# Adafruit_Arcade_Bonnet.net
KiCad netlist of a schematic drawn in EAGLE
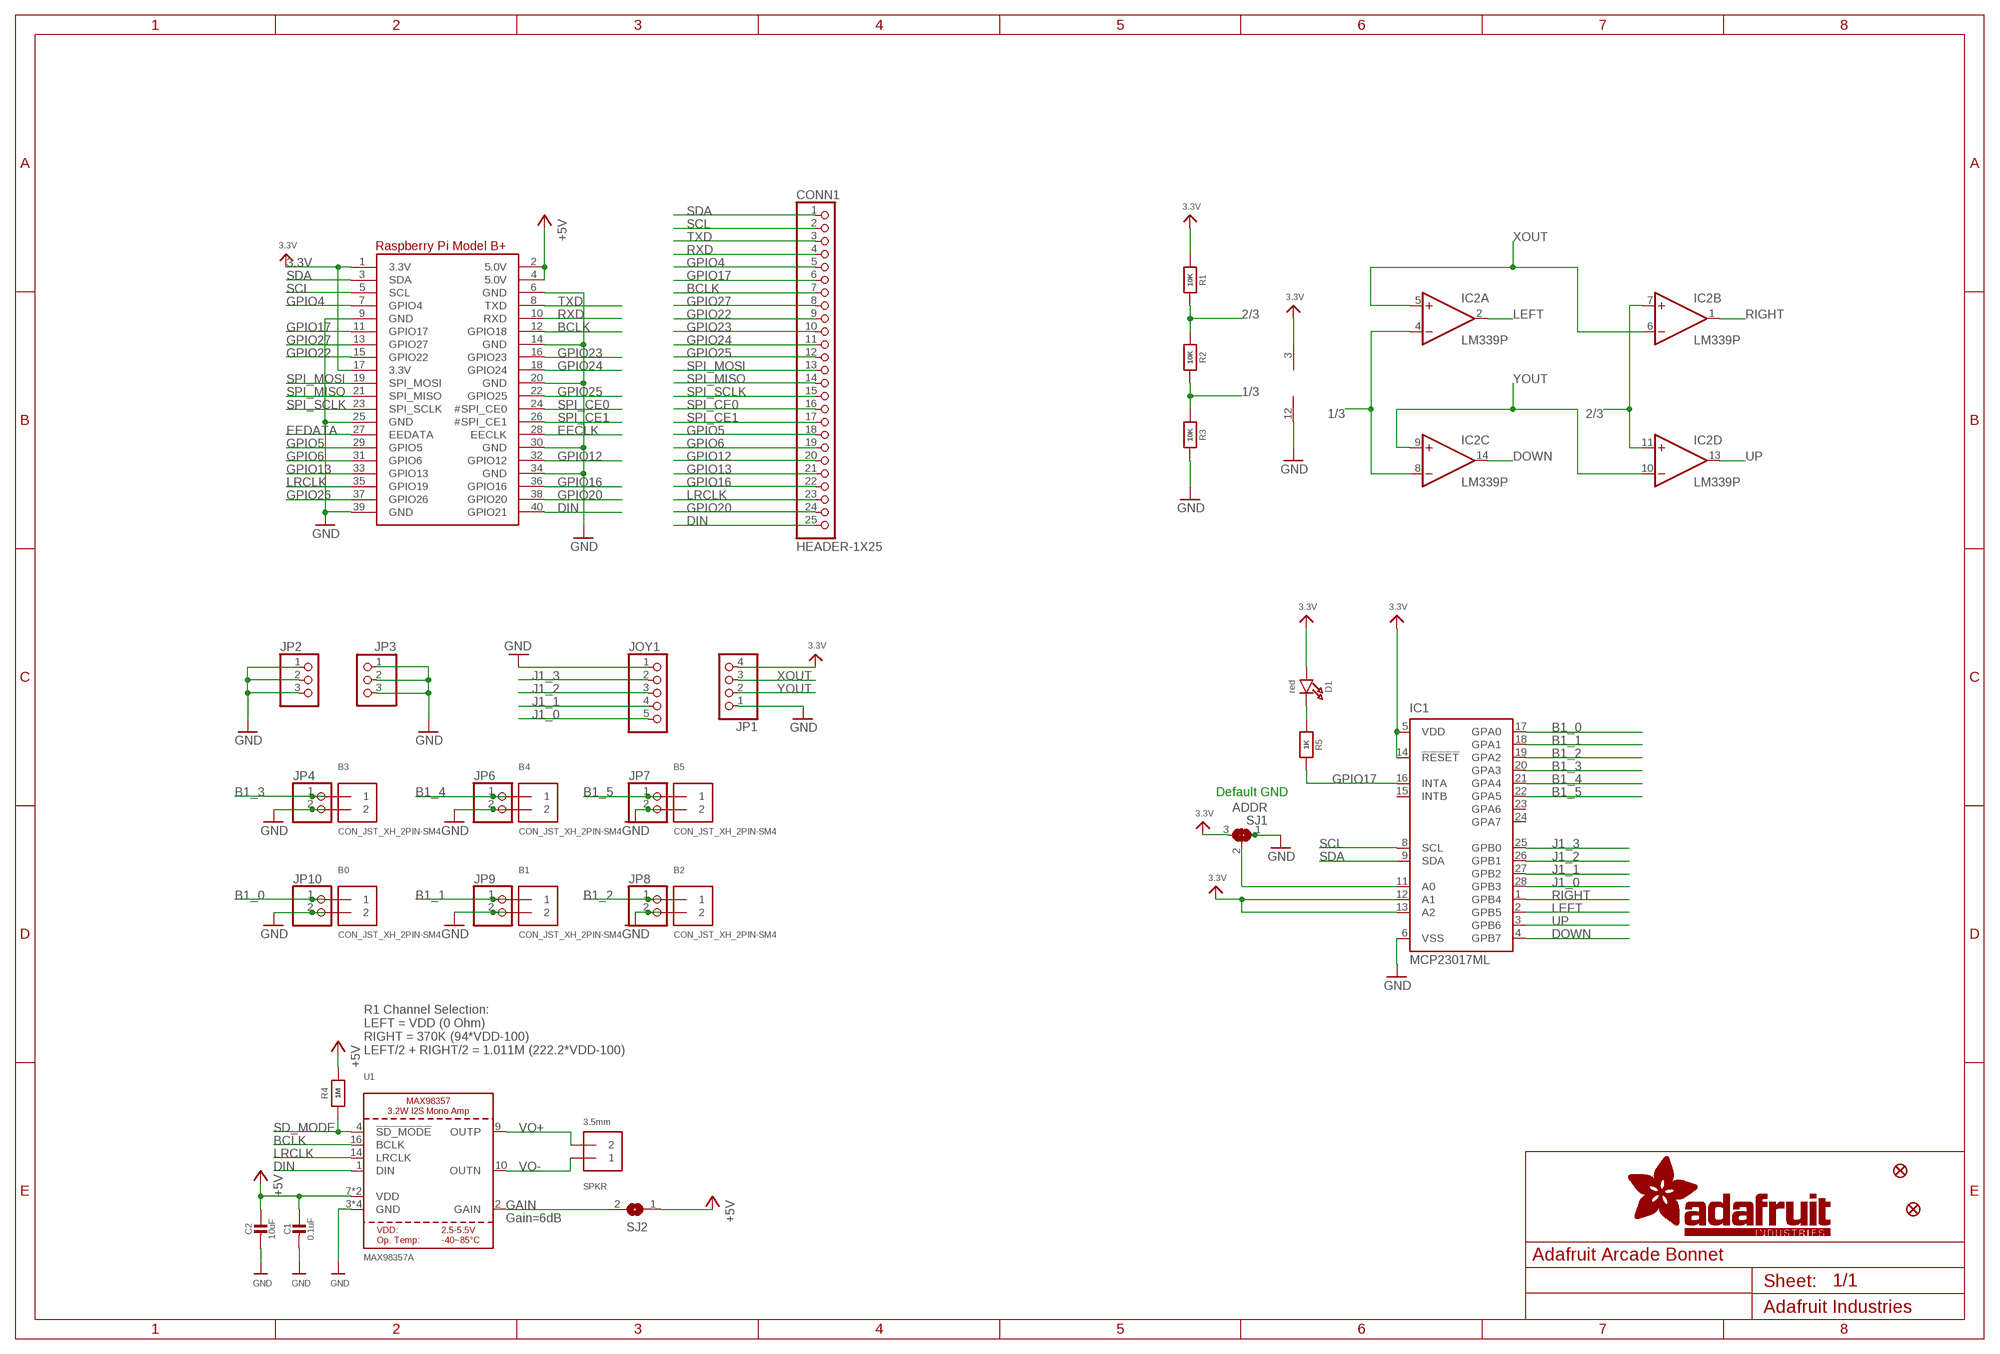
[diagram p0: schematic, sheet 1]

(export (version "E")
  (design (tool "Eeschema 10.0.6"))
  (components
    (comp (ref "B0")
      (value "CON_JST_XH_2PIN-SM4")
      (footprint "eagle-import:JST-XH-2-SM4")
      (libsource (lib "eagle-import") (part "CON_JST_XH_2PIN-SM4"))
    )
    (comp (ref "B1")
      (value "CON_JST_XH_2PIN-SM4")
      (footprint "eagle-import:JST-XH-2-SM4")
      (libsource (lib "eagle-import") (part "CON_JST_XH_2PIN-SM4"))
    )
    (comp (ref "B2")
      (value "CON_JST_XH_2PIN-SM4")
      (footprint "eagle-import:JST-XH-2-SM4")
      (libsource (lib "eagle-import") (part "CON_JST_XH_2PIN-SM4"))
    )
    (comp (ref "B3")
      (value "CON_JST_XH_2PIN-SM4")
      (footprint "eagle-import:JST-XH-2-SM4")
      (libsource (lib "eagle-import") (part "CON_JST_XH_2PIN-SM4"))
    )
    (comp (ref "B4")
      (value "CON_JST_XH_2PIN-SM4")
      (footprint "eagle-import:JST-XH-2-SM4")
      (libsource (lib "eagle-import") (part "CON_JST_XH_2PIN-SM4"))
    )
    (comp (ref "B5")
      (value "CON_JST_XH_2PIN-SM4")
      (footprint "eagle-import:JST-XH-2-SM4")
      (libsource (lib "eagle-import") (part "CON_JST_XH_2PIN-SM4"))
    )
    (comp (ref "C1")
      (value "0.1uF")
      (footprint "eagle-import:0603-NO")
      (libsource (lib "eagle-import") (part "CAP_CERAMIC0603_NO"))
    )
    (comp (ref "C2")
      (value "10uF")
      (footprint "eagle-import:0805-NO")
      (libsource (lib "eagle-import") (part "CAP_CERAMIC0805-NOOUTLINE"))
    )
    (comp (ref "CONN1")
      (value "HEADER-1X25")
      (footprint "eagle-import:1X25_ROUND_70MIL")
      (libsource (lib "eagle-import") (part "HEADER-1X25"))
    )
    (comp (ref "D1")
      (value "red")
      (footprint "eagle-import:CHIPLED_0805_NOOUTLINE")
      (libsource (lib "eagle-import") (part "LED0805_NOOUTLINE"))
    )
    (comp (ref "FID2")
      (value "FIDUCIAL\"\"")
      (footprint "eagle-import:FIDUCIAL_1MM")
      (libsource (lib "eagle-import") (part "FIDUCIAL{dblquote}{dblquote}"))
    )
    (comp (ref "FID3")
      (value "FIDUCIAL\"\"")
      (footprint "eagle-import:FIDUCIAL_1MM")
      (libsource (lib "eagle-import") (part "FIDUCIAL{dblquote}{dblquote}"))
    )
    (comp (ref "IC1")
      (value "MCP23017ML")
      (footprint "eagle-import:QFN28-ML_6X6MM")
      (fields
        (field (name "MF") "MICROCHIP")
        (field (name "MPN") "MCP23017-E/ML")
        (field (name "MPN_1") "MCP23017-E/SS")
        (field (name "OC_FARNELL") "1467674")
        (field (name "OC_NEWARK") "31K2960")
      )
      (libsource (lib "eagle-import") (part "MCP23017ML"))
    )
    (comp (ref "IC2")
      (value "LM339P")
      (footprint "eagle-import:TSSOP14")
      (libsource (lib "eagle-import") (part "LM339P"))
    )
    (comp (ref "JOY1")
      (value "HEADER-1X5")
      (footprint "eagle-import:1X05_OVAL")
      (libsource (lib "eagle-import") (part "HEADER-1X5"))
    )
    (comp (ref "JP1")
      (value "HEADER-1X4")
      (footprint "eagle-import:1X04_OVAL")
      (libsource (lib "eagle-import") (part "HEADER-1X4"))
    )
    (comp (ref "JP2")
      (value "HEADER-1X3ROUND")
      (footprint "eagle-import:1X03_ROUND")
      (libsource (lib "eagle-import") (part "HEADER-1X3ROUND"))
    )
    (comp (ref "JP3")
      (value "HEADER-1X3ROUND")
      (footprint "eagle-import:1X03_ROUND")
      (libsource (lib "eagle-import") (part "HEADER-1X3ROUND"))
    )
    (comp (ref "JP4")
      (value "HEADER-1X2")
      (footprint "eagle-import:1X02_OVAL")
      (libsource (lib "eagle-import") (part "HEADER-1X2"))
    )
    (comp (ref "JP6")
      (value "HEADER-1X2")
      (footprint "eagle-import:1X02_OVAL")
      (libsource (lib "eagle-import") (part "HEADER-1X2"))
    )
    (comp (ref "JP7")
      (value "HEADER-1X2")
      (footprint "eagle-import:1X02_OVAL")
      (libsource (lib "eagle-import") (part "HEADER-1X2"))
    )
    (comp (ref "JP8")
      (value "HEADER-1X2")
      (footprint "eagle-import:1X02_OVAL")
      (libsource (lib "eagle-import") (part "HEADER-1X2"))
    )
    (comp (ref "JP9")
      (value "HEADER-1X2")
      (footprint "eagle-import:1X02_OVAL")
      (libsource (lib "eagle-import") (part "HEADER-1X2"))
    )
    (comp (ref "JP10")
      (value "HEADER-1X2")
      (footprint "eagle-import:1X02_OVAL")
      (libsource (lib "eagle-import") (part "HEADER-1X2"))
    )
    (comp (ref "R1")
      (value "10K")
      (footprint "eagle-import:0805_10MGAP")
      (libsource (lib "eagle-import") (part "RESISTOR0805_10MGAP"))
    )
    (comp (ref "R2")
      (value "10K")
      (footprint "eagle-import:0805-NO")
      (libsource (lib "eagle-import") (part "RESISTOR0805_NOOUTLINE"))
    )
    (comp (ref "R3")
      (value "10K")
      (footprint "eagle-import:0805-NO")
      (libsource (lib "eagle-import") (part "RESISTOR0805_NOOUTLINE"))
    )
    (comp (ref "R4")
      (value "1M")
      (footprint "eagle-import:0603-NO")
      (libsource (lib "eagle-import") (part "RESISTOR_0603_NOOUT"))
    )
    (comp (ref "R5")
      (value "1K")
      (footprint "eagle-import:0603-NO")
      (libsource (lib "eagle-import") (part "RESISTOR_0603_NOOUT"))
    )
    (comp (ref "RPI1")
      (value "RASPBERRYPI_BPLUS_PHAT")
      (footprint "eagle-import:PI_BONNET")
      (libsource (lib "eagle-import") (part "RASPBERRYPI_BPLUS_PHAT"))
    )
    (comp (ref "SJ1")
      (value "ADDR")
      (footprint "eagle-import:SOLDERJUMPER_2WAY_OPEN_NOPASTE")
      (libsource (lib "eagle-import") (part "SOLDERJUMPER_2WAY"))
    )
    (comp (ref "SJ2")
      (value "SOLDERJUMPERCLOSED")
      (footprint "eagle-import:SOLDERJUMPER_CLOSEDWIRE")
      (libsource (lib "eagle-import") (part "SOLDERJUMPERCLOSED"))
    )
    (comp (ref "SPKR")
      (value "3.5mm")
      (footprint "eagle-import:TERMBLOCK_1X2-3.5MM")
      (libsource (lib "eagle-import") (part "TERMBLOCK_1X2"))
    )
    (comp (ref "U1")
      (value "MAX98357A")
      (footprint "eagle-import:QFN16_3MM")
      (libsource (lib "eagle-import") (part "AUDIOAMP_MAX98357"))
    )
  )
  (nets
    (net (code "1") (name "+5V") (class "Default")
      (node (ref "C1") (pin "1") (pinfunction "1_1") (pintype "passive"))
      (node (ref "C2") (pin "1") (pinfunction "1_1") (pintype "passive"))
      (node (ref "R4") (pin "2") (pinfunction "2_2") (pintype "passive"))
      (node (ref "RPI1") (pin "2") (pinfunction "5.0V_2") (pintype "power_in"))
      (node (ref "RPI1") (pin "4") (pinfunction "5.0V_4") (pintype "power_in"))
      (node (ref "SJ2") (pin "1") (pinfunction "1_1") (pintype "passive"))
      (node (ref "U1") (pin "7") (pinfunction "VDD_7") (pintype "power_in"))
      (node (ref "U1") (pin "8") (pinfunction "VDD_8") (pintype "power_in"))
    )
    (net (code "2") (name "/1{slash}3") (class "Default")
      (node (ref "IC2") (pin "4") (pinfunction "-IN_4") (pintype "input"))
      (node (ref "IC2") (pin "8") (pinfunction "-IN_8") (pintype "input"))
      (node (ref "R2") (pin "2") (pinfunction "2_2") (pintype "passive"))
      (node (ref "R3") (pin "1") (pinfunction "1_1") (pintype "passive"))
    )
    (net (code "3") (name "/2{slash}3") (class "Default")
      (node (ref "IC2") (pin "11") (pinfunction "+IN_11") (pintype "input"))
      (node (ref "IC2") (pin "7") (pinfunction "+IN_7") (pintype "input"))
      (node (ref "R1") (pin "2") (pinfunction "2_2") (pintype "passive"))
      (node (ref "R2") (pin "1") (pinfunction "1_1") (pintype "passive"))
    )
    (net (code "4") (name "/B1_0") (class "Default")
      (node (ref "B0") (pin "1") (pinfunction "1_1") (pintype "passive"))
      (node (ref "IC1") (pin "17") (pinfunction "GPA0_17") (pintype "bidirectional"))
      (node (ref "JP10") (pin "1") (pinfunction "1_1") (pintype "passive"))
    )
    (net (code "5") (name "/B1_1") (class "Default")
      (node (ref "B1") (pin "1") (pinfunction "1_1") (pintype "passive"))
      (node (ref "IC1") (pin "18") (pinfunction "GPA1_18") (pintype "bidirectional"))
      (node (ref "JP9") (pin "1") (pinfunction "1_1") (pintype "passive"))
    )
    (net (code "6") (name "/B1_2") (class "Default")
      (node (ref "B2") (pin "1") (pinfunction "1_1") (pintype "passive"))
      (node (ref "IC1") (pin "19") (pinfunction "GPA2_19") (pintype "bidirectional"))
      (node (ref "JP8") (pin "1") (pinfunction "1_1") (pintype "passive"))
    )
    (net (code "7") (name "/B1_3") (class "Default")
      (node (ref "B3") (pin "1") (pinfunction "1_1") (pintype "passive"))
      (node (ref "IC1") (pin "20") (pinfunction "GPA3_20") (pintype "bidirectional"))
      (node (ref "JP4") (pin "1") (pinfunction "1_1") (pintype "passive"))
    )
    (net (code "8") (name "/B1_4") (class "Default")
      (node (ref "B4") (pin "1") (pinfunction "1_1") (pintype "passive"))
      (node (ref "IC1") (pin "21") (pinfunction "GPA4_21") (pintype "bidirectional"))
      (node (ref "JP6") (pin "1") (pinfunction "1_1") (pintype "passive"))
    )
    (net (code "9") (name "/B1_5") (class "Default")
      (node (ref "B5") (pin "1") (pinfunction "1_1") (pintype "passive"))
      (node (ref "IC1") (pin "22") (pinfunction "GPA5_22") (pintype "bidirectional"))
      (node (ref "JP7") (pin "1") (pinfunction "1_1") (pintype "passive"))
    )
    (net (code "10") (name "/BCLK") (class "Default")
      (node (ref "CONN1") (pin "7") (pinfunction "7_7") (pintype "passive"))
      (node (ref "RPI1") (pin "12") (pinfunction "GPIO18_12") (pintype "bidirectional"))
      (node (ref "U1") (pin "16") (pinfunction "BCLK_16") (pintype "bidirectional"))
    )
    (net (code "11") (name "/DIN") (class "Default")
      (node (ref "CONN1") (pin "25") (pinfunction "25_25") (pintype "passive"))
      (node (ref "RPI1") (pin "40") (pinfunction "GPIO21_40") (pintype "bidirectional"))
      (node (ref "U1") (pin "1") (pinfunction "DIN_1") (pintype "bidirectional"))
    )
    (net (code "12") (name "/DOWN") (class "Default")
      (node (ref "IC1") (pin "4") (pinfunction "GPB7_4") (pintype "bidirectional"))
      (node (ref "IC2") (pin "14") (pinfunction "OUT_14") (pintype "open_collector"))
    )
    (net (code "13") (name "/EECLK") (class "Default")
      (node (ref "RPI1") (pin "28") (pinfunction "EECLK_28") (pintype "bidirectional"))
    )
    (net (code "14") (name "/EEDATA") (class "Default")
      (node (ref "RPI1") (pin "27") (pinfunction "EEDATA_27") (pintype "bidirectional"))
    )
    (net (code "15") (name "/GAIN") (class "Default")
      (node (ref "SJ2") (pin "2") (pinfunction "2_2") (pintype "passive"))
      (node (ref "U1") (pin "2") (pinfunction "GAIN_2") (pintype "bidirectional"))
    )
    (net (code "16") (name "/GPIO4") (class "Default")
      (node (ref "CONN1") (pin "5") (pinfunction "5_5") (pintype "passive"))
      (node (ref "RPI1") (pin "7") (pinfunction "GPIO4_7") (pintype "bidirectional"))
    )
    (net (code "17") (name "/GPIO5") (class "Default")
      (node (ref "CONN1") (pin "18") (pinfunction "18_18") (pintype "passive"))
      (node (ref "RPI1") (pin "29") (pinfunction "GPIO5_29") (pintype "bidirectional"))
    )
    (net (code "18") (name "/GPIO6") (class "Default")
      (node (ref "CONN1") (pin "19") (pinfunction "19_19") (pintype "passive"))
      (node (ref "RPI1") (pin "31") (pinfunction "GPIO6_31") (pintype "bidirectional"))
    )
    (net (code "19") (name "/GPIO12") (class "Default")
      (node (ref "CONN1") (pin "20") (pinfunction "20_20") (pintype "passive"))
      (node (ref "RPI1") (pin "32") (pinfunction "GPIO12_32") (pintype "bidirectional"))
    )
    (net (code "20") (name "/GPIO13") (class "Default")
      (node (ref "CONN1") (pin "21") (pinfunction "21_21") (pintype "passive"))
      (node (ref "RPI1") (pin "33") (pinfunction "GPIO13_33") (pintype "bidirectional"))
    )
    (net (code "21") (name "/GPIO16") (class "Default")
      (node (ref "CONN1") (pin "22") (pinfunction "22_22") (pintype "passive"))
      (node (ref "RPI1") (pin "36") (pinfunction "GPIO16_36") (pintype "bidirectional"))
    )
    (net (code "22") (name "/GPIO17") (class "Default")
      (node (ref "CONN1") (pin "6") (pinfunction "6_6") (pintype "passive"))
      (node (ref "IC1") (pin "16") (pinfunction "INTA_16") (pintype "output"))
      (node (ref "R5") (pin "2") (pinfunction "2_2") (pintype "passive"))
      (node (ref "RPI1") (pin "11") (pinfunction "GPIO17_11") (pintype "bidirectional"))
    )
    (net (code "23") (name "/GPIO20") (class "Default")
      (node (ref "CONN1") (pin "24") (pinfunction "24_24") (pintype "passive"))
      (node (ref "RPI1") (pin "38") (pinfunction "GPIO20_38") (pintype "bidirectional"))
    )
    (net (code "24") (name "/GPIO22") (class "Default")
      (node (ref "CONN1") (pin "9") (pinfunction "9_9") (pintype "passive"))
      (node (ref "RPI1") (pin "15") (pinfunction "GPIO22_15") (pintype "bidirectional"))
    )
    (net (code "25") (name "/GPIO23") (class "Default")
      (node (ref "CONN1") (pin "10") (pinfunction "10_10") (pintype "passive"))
      (node (ref "RPI1") (pin "16") (pinfunction "GPIO23_16") (pintype "bidirectional"))
    )
    (net (code "26") (name "/GPIO24") (class "Default")
      (node (ref "CONN1") (pin "11") (pinfunction "11_11") (pintype "passive"))
      (node (ref "RPI1") (pin "18") (pinfunction "GPIO24_18") (pintype "bidirectional"))
    )
    (net (code "27") (name "/GPIO25") (class "Default")
      (node (ref "CONN1") (pin "12") (pinfunction "12_12") (pintype "passive"))
      (node (ref "RPI1") (pin "22") (pinfunction "GPIO25_22") (pintype "bidirectional"))
    )
    (net (code "28") (name "/GPIO26") (class "Default")
      (node (ref "RPI1") (pin "37") (pinfunction "GPIO26_37") (pintype "bidirectional"))
    )
    (net (code "29") (name "/GPIO27") (class "Default")
      (node (ref "CONN1") (pin "8") (pinfunction "8_8") (pintype "passive"))
      (node (ref "RPI1") (pin "13") (pinfunction "GPIO27_13") (pintype "bidirectional"))
    )
    (net (code "30") (name "/J1_0") (class "Default")
      (node (ref "IC1") (pin "28") (pinfunction "GPB3_28") (pintype "bidirectional"))
      (node (ref "JOY1") (pin "5") (pinfunction "5_5") (pintype "passive"))
    )
    (net (code "31") (name "/J1_1") (class "Default")
      (node (ref "IC1") (pin "27") (pinfunction "GPB2_27") (pintype "bidirectional"))
      (node (ref "JOY1") (pin "4") (pinfunction "4_4") (pintype "passive"))
    )
    (net (code "32") (name "/J1_2") (class "Default")
      (node (ref "IC1") (pin "26") (pinfunction "GPB1_26") (pintype "bidirectional"))
      (node (ref "JOY1") (pin "3") (pinfunction "3_3") (pintype "passive"))
    )
    (net (code "33") (name "/J1_3") (class "Default")
      (node (ref "IC1") (pin "25") (pinfunction "GPB0_25") (pintype "bidirectional"))
      (node (ref "JOY1") (pin "2") (pinfunction "2_2") (pintype "passive"))
    )
    (net (code "34") (name "/LEFT") (class "Default")
      (node (ref "IC1") (pin "2") (pinfunction "GPB5_2") (pintype "bidirectional"))
      (node (ref "IC2") (pin "2") (pinfunction "OUT_2") (pintype "open_collector"))
    )
    (net (code "35") (name "/LRCLK") (class "Default")
      (node (ref "CONN1") (pin "23") (pinfunction "23_23") (pintype "passive"))
      (node (ref "RPI1") (pin "35") (pinfunction "GPIO19_35") (pintype "bidirectional"))
      (node (ref "U1") (pin "14") (pinfunction "LRCLK_14") (pintype "bidirectional"))
    )
    (net (code "36") (name "/RIGHT") (class "Default")
      (node (ref "IC1") (pin "1") (pinfunction "GPB4_1") (pintype "bidirectional"))
      (node (ref "IC2") (pin "1") (pinfunction "OUT_1") (pintype "open_collector"))
    )
    (net (code "37") (name "/RXD") (class "Default")
      (node (ref "CONN1") (pin "4") (pinfunction "4_4") (pintype "passive"))
      (node (ref "RPI1") (pin "10") (pinfunction "RXD_10") (pintype "bidirectional"))
    )
    (net (code "38") (name "/SCL") (class "Default")
      (node (ref "CONN1") (pin "2") (pinfunction "2_2") (pintype "passive"))
      (node (ref "IC1") (pin "8") (pinfunction "SCL_8") (pintype "input"))
      (node (ref "RPI1") (pin "5") (pinfunction "SCL_5") (pintype "bidirectional"))
    )
    (net (code "39") (name "/SDA") (class "Default")
      (node (ref "CONN1") (pin "1") (pinfunction "1_1") (pintype "passive"))
      (node (ref "IC1") (pin "9") (pinfunction "SDA_9") (pintype "bidirectional"))
      (node (ref "RPI1") (pin "3") (pinfunction "SDA_3") (pintype "bidirectional"))
    )
    (net (code "40") (name "/SD_MODE") (class "Default")
      (node (ref "R4") (pin "1") (pinfunction "1_1") (pintype "passive"))
      (node (ref "U1") (pin "4") (pinfunction "~{SD_MODE}_4") (pintype "bidirectional"))
    )
    (net (code "41") (name "/SPI_CE0") (class "Default")
      (node (ref "CONN1") (pin "16") (pinfunction "16_16") (pintype "passive"))
      (node (ref "RPI1") (pin "24") (pinfunction "#SPI_CE0_24") (pintype "bidirectional"))
    )
    (net (code "42") (name "/SPI_CE1") (class "Default")
      (node (ref "CONN1") (pin "17") (pinfunction "17_17") (pintype "passive"))
      (node (ref "RPI1") (pin "26") (pinfunction "#SPI_CE1_26") (pintype "bidirectional"))
    )
    (net (code "43") (name "/SPI_MISO") (class "Default")
      (node (ref "CONN1") (pin "14") (pinfunction "14_14") (pintype "passive"))
      (node (ref "RPI1") (pin "21") (pinfunction "SPI_MISO_21") (pintype "bidirectional"))
    )
    (net (code "44") (name "/SPI_MOSI") (class "Default")
      (node (ref "CONN1") (pin "13") (pinfunction "13_13") (pintype "passive"))
      (node (ref "RPI1") (pin "19") (pinfunction "SPI_MOSI_19") (pintype "bidirectional"))
    )
    (net (code "45") (name "/SPI_SCLK") (class "Default")
      (node (ref "CONN1") (pin "15") (pinfunction "15_15") (pintype "passive"))
      (node (ref "RPI1") (pin "23") (pinfunction "SPI_SCLK_23") (pintype "bidirectional"))
    )
    (net (code "46") (name "/TXD") (class "Default")
      (node (ref "CONN1") (pin "3") (pinfunction "3_3") (pintype "passive"))
      (node (ref "RPI1") (pin "8") (pinfunction "TXD_8") (pintype "bidirectional"))
    )
    (net (code "47") (name "/UP") (class "Default")
      (node (ref "IC1") (pin "3") (pinfunction "GPB6_3") (pintype "bidirectional"))
      (node (ref "IC2") (pin "13") (pinfunction "OUT_13") (pintype "open_collector"))
    )
    (net (code "48") (name "/VO+") (class "Default")
      (node (ref "SPKR") (pin "2") (pinfunction "2_2") (pintype "passive"))
      (node (ref "U1") (pin "9") (pinfunction "OUTP_9") (pintype "output"))
    )
    (net (code "49") (name "/VO-") (class "Default")
      (node (ref "SPKR") (pin "1") (pinfunction "1_1") (pintype "passive"))
      (node (ref "U1") (pin "10") (pinfunction "OUTN_10") (pintype "output"))
    )
    (net (code "50") (name "/XOUT") (class "Default")
      (node (ref "IC2") (pin "5") (pinfunction "+IN_5") (pintype "input"))
      (node (ref "IC2") (pin "6") (pinfunction "-IN_6") (pintype "input"))
      (node (ref "JP1") (pin "3") (pinfunction "3_3") (pintype "passive"))
    )
    (net (code "51") (name "/YOUT") (class "Default")
      (node (ref "IC2") (pin "10") (pinfunction "-IN_10") (pintype "input"))
      (node (ref "IC2") (pin "9") (pinfunction "+IN_9") (pintype "input"))
      (node (ref "JP1") (pin "2") (pinfunction "2_2") (pintype "passive"))
    )
    (net (code "52") (name "3.3V") (class "Default")
      (node (ref "D1") (pin "A") (pinfunction "A_A") (pintype "passive"))
      (node (ref "IC1") (pin "12") (pinfunction "A1_12") (pintype "input"))
      (node (ref "IC1") (pin "13") (pinfunction "A2_13") (pintype "input"))
      (node (ref "IC1") (pin "14") (pinfunction "~{RESET}_14") (pintype "input"))
      (node (ref "IC1") (pin "5") (pinfunction "VDD_5") (pintype "power_in"))
      (node (ref "IC2") (pin "3") (pinfunction "V+_3") (pintype "power_in"))
      (node (ref "JP1") (pin "4") (pinfunction "4_4") (pintype "passive"))
      (node (ref "R1") (pin "1") (pinfunction "1_1") (pintype "passive"))
      (node (ref "RPI1") (pin "1") (pinfunction "3.3V_1") (pintype "power_in"))
      (node (ref "RPI1") (pin "17") (pinfunction "3.3V_17") (pintype "power_in"))
      (node (ref "SJ1") (pin "3") (pinfunction "3_3") (pintype "passive"))
    )
    (net (code "53") (name "GND") (class "Default")
      (node (ref "B0") (pin "2") (pinfunction "2_2") (pintype "passive"))
      (node (ref "B1") (pin "2") (pinfunction "2_2") (pintype "passive"))
      (node (ref "B2") (pin "2") (pinfunction "2_2") (pintype "passive"))
      (node (ref "B3") (pin "2") (pinfunction "2_2") (pintype "passive"))
      (node (ref "B4") (pin "2") (pinfunction "2_2") (pintype "passive"))
      (node (ref "B5") (pin "2") (pinfunction "2_2") (pintype "passive"))
      (node (ref "C1") (pin "2") (pinfunction "2_2") (pintype "passive"))
      (node (ref "C2") (pin "2") (pinfunction "2_2") (pintype "passive"))
      (node (ref "IC1") (pin "6") (pinfunction "VSS_6") (pintype "power_in"))
      (node (ref "IC2") (pin "12") (pinfunction "GND_12") (pintype "power_in"))
      (node (ref "JOY1") (pin "1") (pinfunction "1_1") (pintype "passive"))
      (node (ref "JP1") (pin "1") (pinfunction "1_1") (pintype "passive"))
      (node (ref "JP10") (pin "2") (pinfunction "2_2") (pintype "passive"))
      (node (ref "JP2") (pin "1") (pinfunction "1_1") (pintype "passive"))
      (node (ref "JP2") (pin "2") (pinfunction "2_2") (pintype "passive"))
      (node (ref "JP2") (pin "3") (pinfunction "3_3") (pintype "passive"))
      (node (ref "JP3") (pin "1") (pinfunction "1_1") (pintype "passive"))
      (node (ref "JP3") (pin "2") (pinfunction "2_2") (pintype "passive"))
      (node (ref "JP3") (pin "3") (pinfunction "3_3") (pintype "passive"))
      (node (ref "JP4") (pin "2") (pinfunction "2_2") (pintype "passive"))
      (node (ref "JP6") (pin "2") (pinfunction "2_2") (pintype "passive"))
      (node (ref "JP7") (pin "2") (pinfunction "2_2") (pintype "passive"))
      (node (ref "JP8") (pin "2") (pinfunction "2_2") (pintype "passive"))
      (node (ref "JP9") (pin "2") (pinfunction "2_2") (pintype "passive"))
      (node (ref "R3") (pin "2") (pinfunction "2_2") (pintype "passive"))
      (node (ref "RPI1") (pin "14") (pinfunction "GND_14") (pintype "power_in"))
      (node (ref "RPI1") (pin "20") (pinfunction "GND_20") (pintype "power_in"))
      (node (ref "RPI1") (pin "25") (pinfunction "GND_25") (pintype "power_in"))
      (node (ref "RPI1") (pin "30") (pinfunction "GND_30") (pintype "power_in"))
      (node (ref "RPI1") (pin "34") (pinfunction "GND_34") (pintype "power_in"))
      (node (ref "RPI1") (pin "39") (pinfunction "GND_39") (pintype "power_in"))
      (node (ref "RPI1") (pin "6") (pinfunction "GND_6") (pintype "power_in"))
      (node (ref "RPI1") (pin "9") (pinfunction "GND_9") (pintype "power_in"))
      (node (ref "SJ1") (pin "1") (pinfunction "1_1") (pintype "passive"))
      (node (ref "U1") (pin "11") (pinfunction "GND_11") (pintype "power_in"))
      (node (ref "U1") (pin "15") (pinfunction "GND_15") (pintype "power_in"))
      (node (ref "U1") (pin "3") (pinfunction "GND_3") (pintype "power_in"))
      (node (ref "U1") (pin "THERMAL") (pinfunction "GND_THERMAL") (pintype "power_in"))
    )
    (net (code "54") (name "Net-(D1-PadC)") (class "Default")
      (node (ref "D1") (pin "C") (pinfunction "C_C") (pintype "passive"))
      (node (ref "R5") (pin "1") (pinfunction "1_1") (pintype "passive"))
    )
    (net (code "55") (name "Net-(IC1-A0)") (class "Default")
      (node (ref "IC1") (pin "11") (pinfunction "A0_11") (pintype "input"))
      (node (ref "SJ1") (pin "2") (pinfunction "2_2") (pintype "passive"))
    )
    (net (code "56") (name "unconnected-(IC1-GPA6-Pad23)") (class "Default")
      (node (ref "IC1") (pin "23") (pinfunction "GPA6_23") (pintype "bidirectional"))
    )
    (net (code "57") (name "unconnected-(IC1-GPA7-Pad24)") (class "Default")
      (node (ref "IC1") (pin "24") (pinfunction "GPA7_24") (pintype "bidirectional"))
    )
    (net (code "58") (name "unconnected-(IC1-INTB-Pad15)") (class "Default")
      (node (ref "IC1") (pin "15") (pinfunction "INTB_15") (pintype "output"))
    )
  )
)
